# audio_spectrum.net
KiCad netlist of a schematic drawn in EAGLE
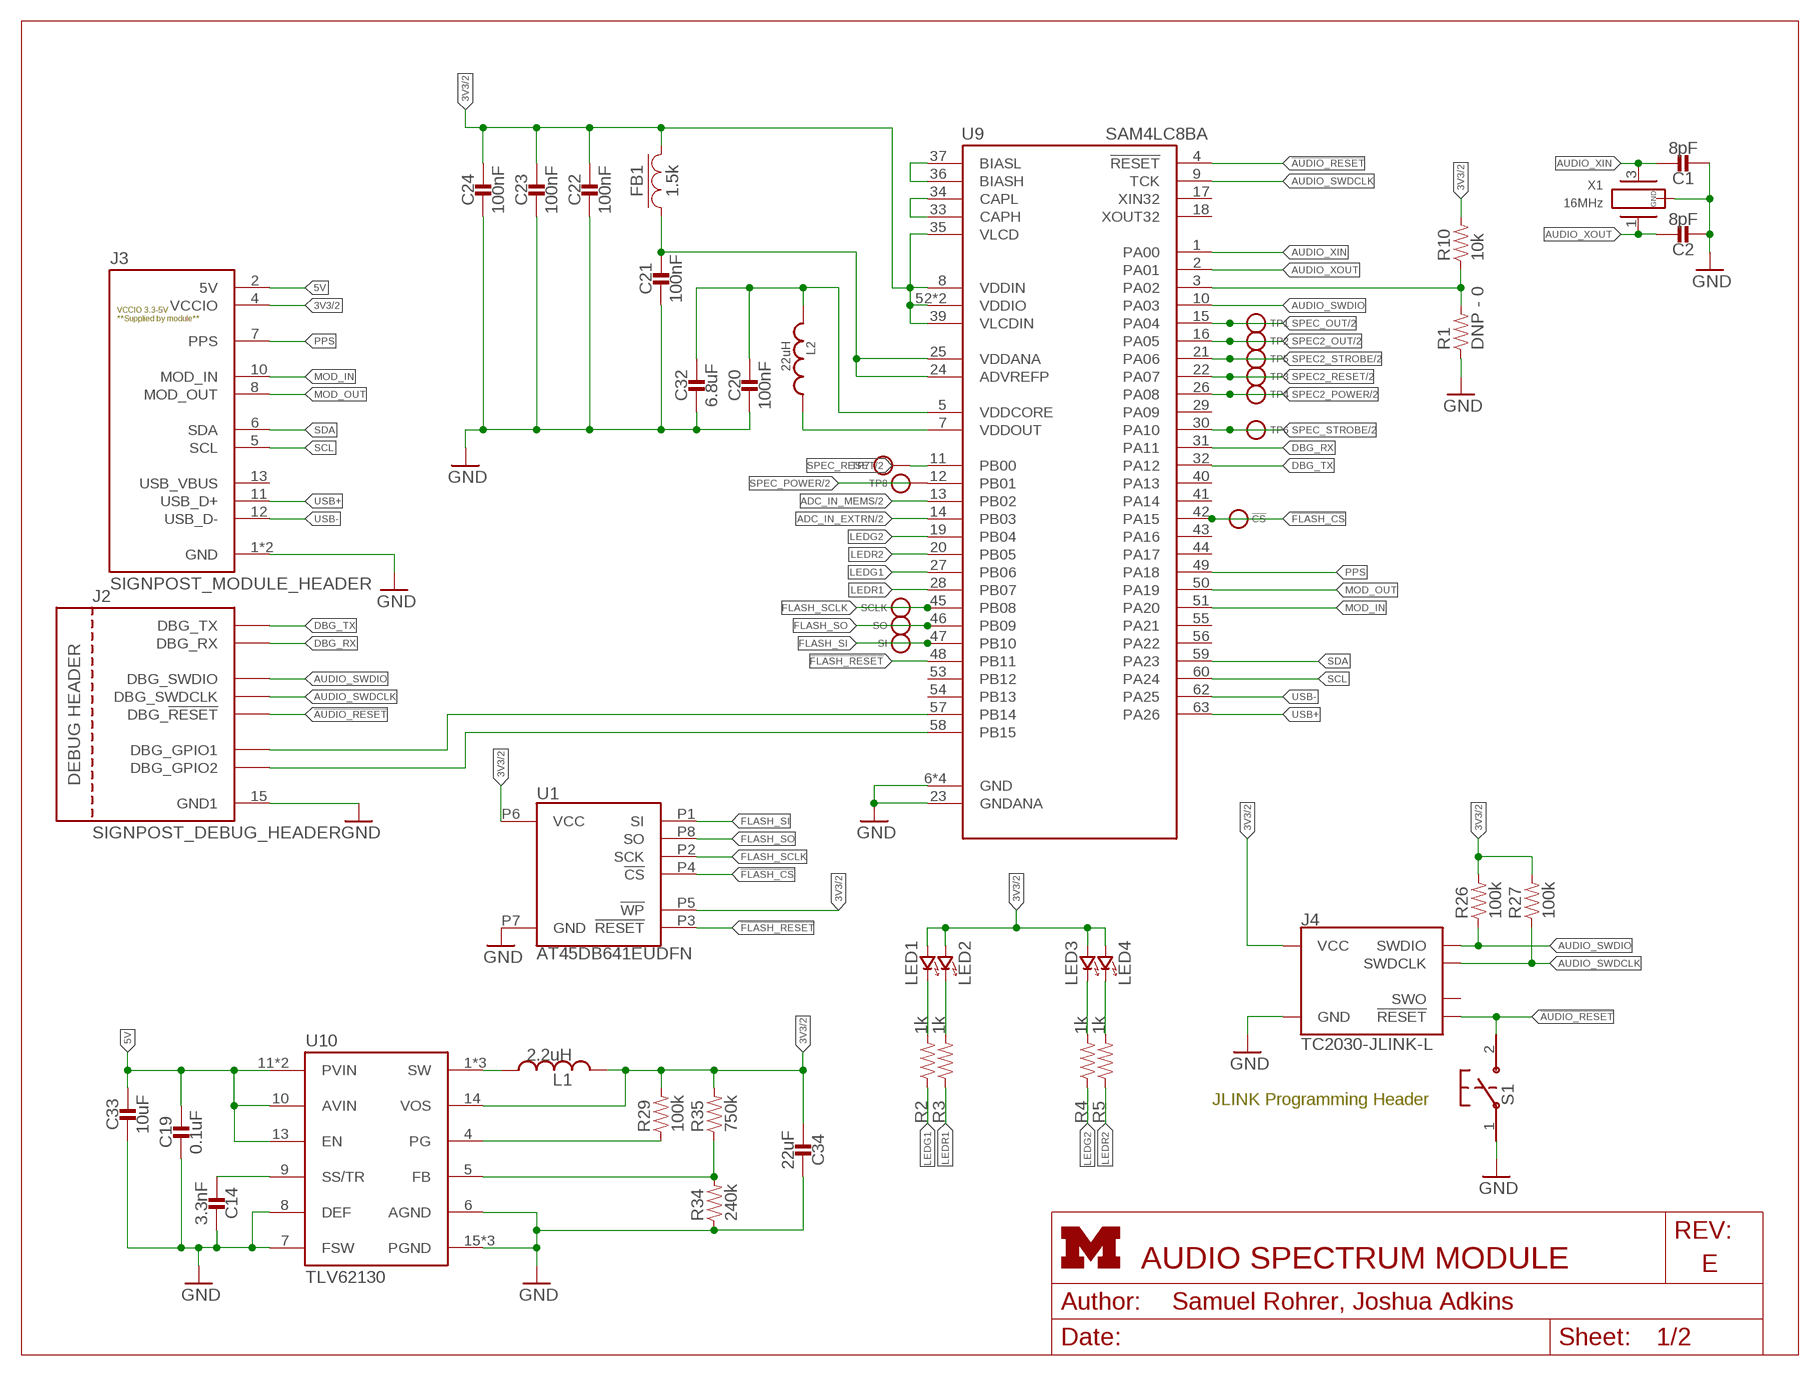
[diagram p0: schematic, sheet 1]
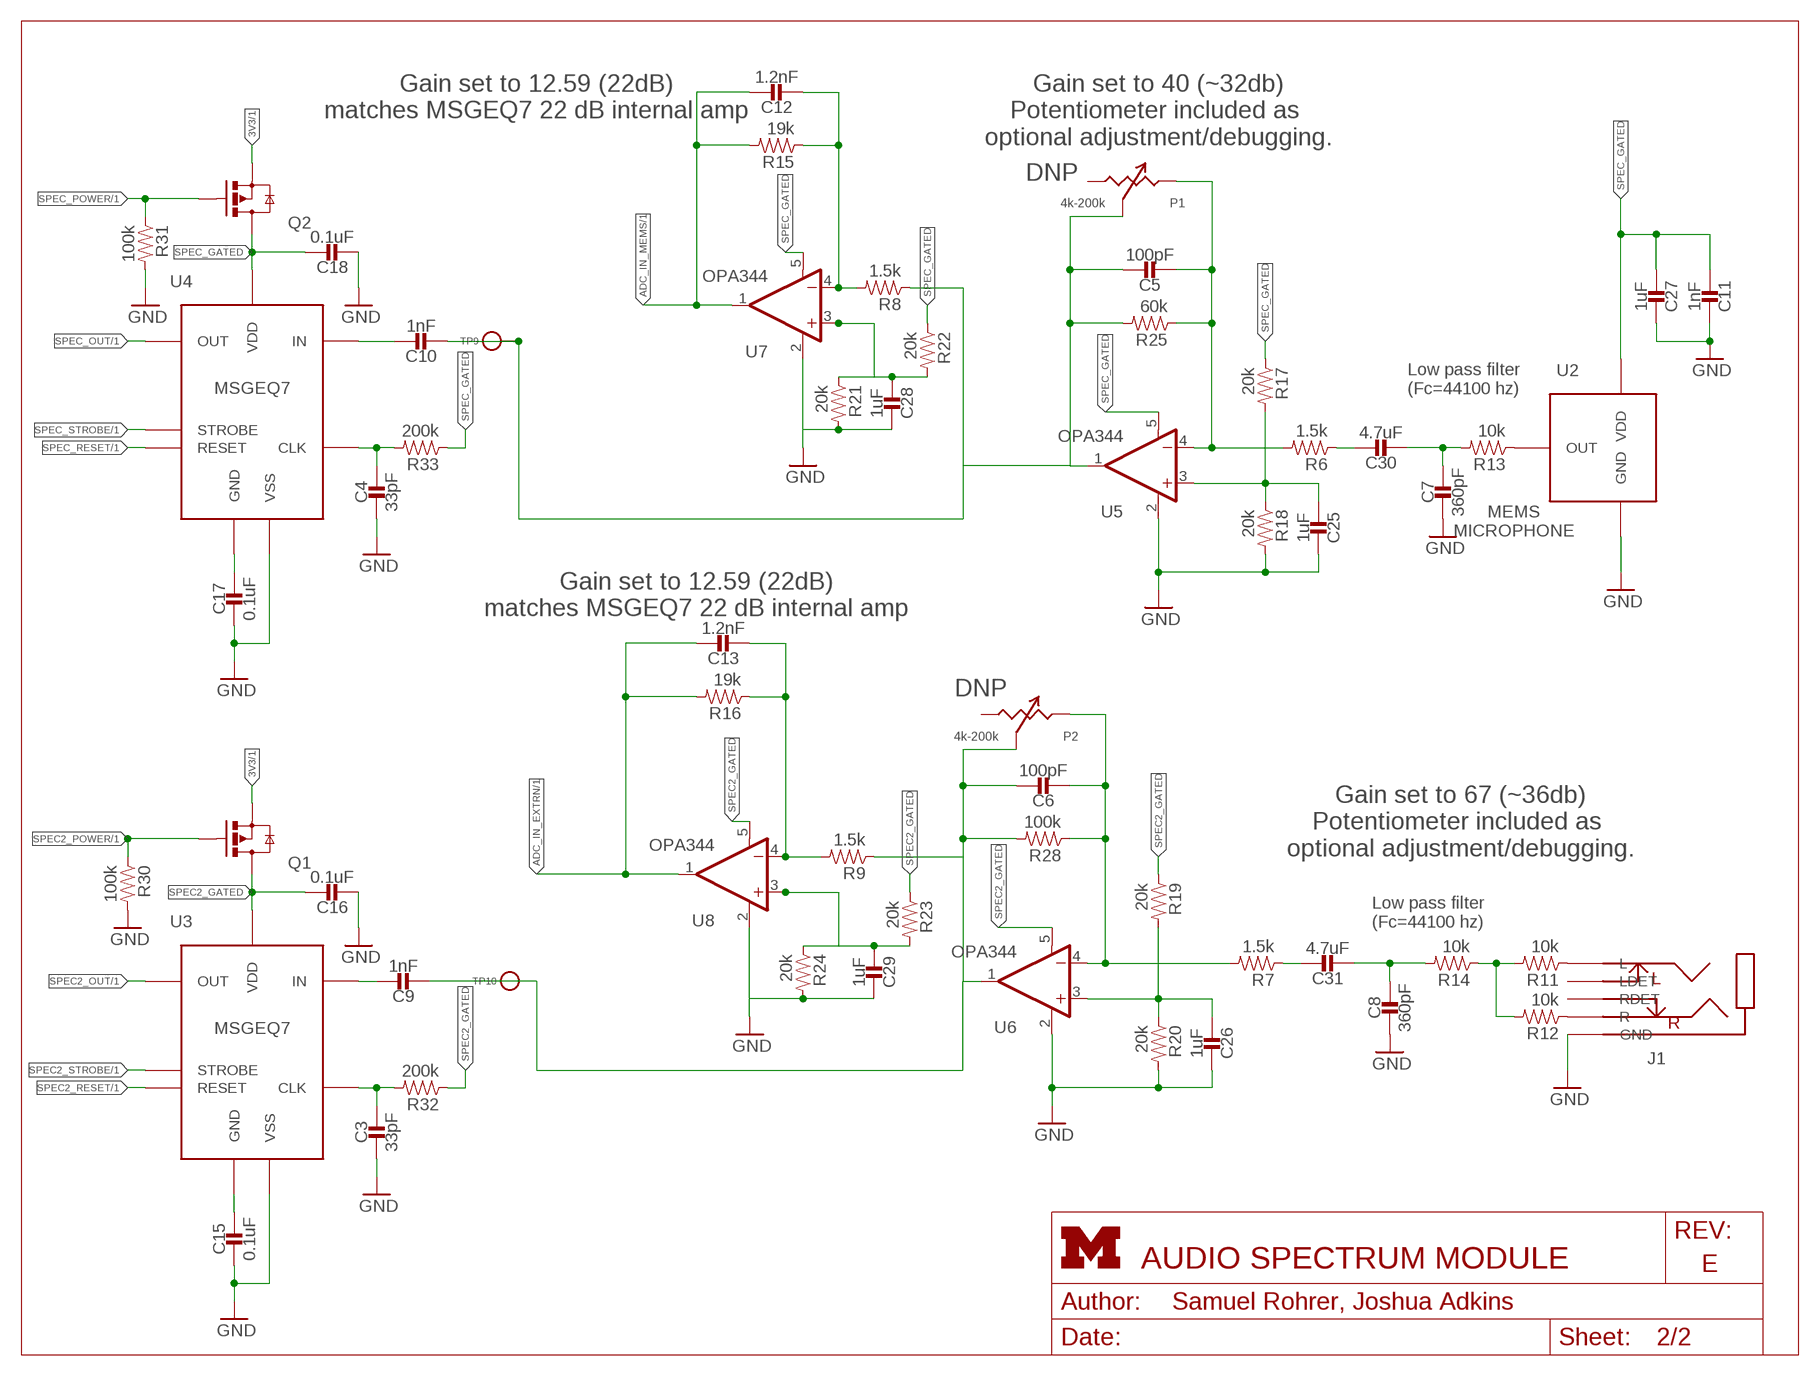
[diagram p1: schematic, sheet 2]

(export (version "E")
  (design (tool "Eeschema 10.0.6"))
  (components
    (comp (ref "C3")
      (value "33pF")
      (footprint "eagle-import:0603_CAP")
      (fields (field (name "MANUFACTURER") "Murata") (field (name "MPN") "GRM1885C1H330JA01D"))
      (libsource (lib "eagle-import") (part "CAPACITOR0603_CAP"))
    )
    (comp (ref "C4")
      (value "33pF")
      (footprint "eagle-import:0603_CAP")
      (fields (field (name "MANUFACTURER") "Murata") (field (name "MPN") "GRM1885C1H330JA01D"))
      (libsource (lib "eagle-import") (part "CAPACITOR0603_CAP"))
    )
    (comp (ref "C5")
      (value "100pF")
      (footprint "eagle-import:0603_CAP")
      (fields (field (name "MANUFACTURER") "Murata") (field (name "MPN") "GRM1885C1H101JA01D"))
      (libsource (lib "eagle-import") (part "CAPACITOR0603_CAP"))
    )
    (comp (ref "C6")
      (value "100pF")
      (footprint "eagle-import:0603_CAP")
      (fields (field (name "MANUFACTURER") "Murata") (field (name "MPN") "GRM1885C1H101JA01D"))
      (libsource (lib "eagle-import") (part "CAPACITOR0603_CAP"))
    )
    (comp (ref "C7")
      (value "360pF")
      (footprint "eagle-import:0603_CAP")
      (fields (field (name "MANUFACTURER") "Murata") (field (name "MPN") "GRM1885C1H361JA01D"))
      (libsource (lib "eagle-import") (part "CAPACITOR0603_CAP"))
    )
    (comp (ref "C8")
      (value "360pF")
      (footprint "eagle-import:0603_CAP")
      (fields (field (name "MANUFACTURER") "Murata") (field (name "MPN") "GRM1885C1H361JA01D"))
      (libsource (lib "eagle-import") (part "CAPACITOR0603_CAP"))
    )
    (comp (ref "C9")
      (value "1nF")
      (footprint "eagle-import:0603_CAP")
      (fields (field (name "MANUFACTURER") "Murata") (field (name "MPN") "GRM188R71H102KA01D"))
      (libsource (lib "eagle-import") (part "CAPACITOR0603_CAP"))
    )
    (comp (ref "C10")
      (value "1nF")
      (footprint "eagle-import:0603_CAP")
      (fields (field (name "MANUFACTURER") "Murata") (field (name "MPN") "GRM188R71H102KA01D"))
      (libsource (lib "eagle-import") (part "CAPACITOR0603_CAP"))
    )
    (comp (ref "C11")
      (value "1nF")
      (footprint "eagle-import:0603_CAP")
      (fields (field (name "MANUFACTURER") "Murata") (field (name "MPN") "GRM188R71H102KA01D"))
      (libsource (lib "eagle-import") (part "CAPACITOR0603_CAP"))
    )
    (comp (ref "C12")
      (value "1.2nF")
      (footprint "eagle-import:0603_CAP")
      (fields (field (name "MANUFACTURER") "Murata") (field (name "MPN") "GCM1885C1H122JA16D"))
      (libsource (lib "eagle-import") (part "CAPACITOR0603_CAP"))
    )
    (comp (ref "C13")
      (value "1.2nF")
      (footprint "eagle-import:0603_CAP")
      (fields (field (name "MANUFACTURER") "Murata") (field (name "MPN") "GCM1885C1H122JA16D"))
      (libsource (lib "eagle-import") (part "CAPACITOR0603_CAP"))
    )
    (comp (ref "C15")
      (value "0.1uF")
      (footprint "eagle-import:0603_CAP")
      (fields (field (name "MANUFACTURER") "Murata") (field (name "MPN") "GRM188R71C104KA01D"))
      (libsource (lib "eagle-import") (part "CAPACITOR0603_CAP"))
    )
    (comp (ref "C16")
      (value "0.1uF")
      (footprint "eagle-import:0603_CAP")
      (fields (field (name "MANUFACTURER") "Murata") (field (name "MPN") "GRM188R71C104KA01D"))
      (libsource (lib "eagle-import") (part "CAPACITOR0603_CAP"))
    )
    (comp (ref "C17")
      (value "0.1uF")
      (footprint "eagle-import:0603_CAP")
      (fields (field (name "MANUFACTURER") "Murata") (field (name "MPN") "GRM188R71C104KA01D"))
      (libsource (lib "eagle-import") (part "CAPACITOR0603_CAP"))
    )
    (comp (ref "C18")
      (value "0.1uF")
      (footprint "eagle-import:0603_CAP")
      (fields (field (name "MANUFACTURER") "Murata") (field (name "MPN") "GRM188R71C104KA01D"))
      (libsource (lib "eagle-import") (part "CAPACITOR0603_CAP"))
    )
    (comp (ref "C25")
      (value "1uF")
      (footprint "eagle-import:0603_CAP")
      (fields (field (name "MANUFACTURER") "Murata") (field (name "MPN") "GRM188R61C105KA93D"))
      (libsource (lib "eagle-import") (part "CAPACITOR0603_CAP"))
    )
    (comp (ref "C26")
      (value "1uF")
      (footprint "eagle-import:0603_CAP")
      (fields (field (name "MANUFACTURER") "Murata") (field (name "MPN") "GRM188R61C105KA93D"))
      (libsource (lib "eagle-import") (part "CAPACITOR0603_CAP"))
    )
    (comp (ref "C27")
      (value "1uF")
      (footprint "eagle-import:0603_CAP")
      (fields (field (name "MANUFACTURER") "Murata") (field (name "MPN") "GRM188R61C105KA93D"))
      (libsource (lib "eagle-import") (part "CAPACITOR0603_CAP"))
    )
    (comp (ref "C28")
      (value "1uF")
      (footprint "eagle-import:0603_CAP")
      (fields (field (name "MANUFACTURER") "Murata") (field (name "MPN") "GRM188R61C105KA93D"))
      (libsource (lib "eagle-import") (part "CAPACITOR0603_CAP"))
    )
    (comp (ref "C29")
      (value "1uF")
      (footprint "eagle-import:0603_CAP")
      (fields (field (name "MANUFACTURER") "Murata") (field (name "MPN") "GRM188R61C105KA93D"))
      (libsource (lib "eagle-import") (part "CAPACITOR0603_CAP"))
    )
    (comp (ref "C30")
      (value "4.7uF")
      (footprint "eagle-import:0603_CAP")
      (fields (field (name "MANUFACTURER") "Murata") (field (name "MPN") "GRM188R60J475KE19D"))
      (libsource (lib "eagle-import") (part "CAPACITOR0603_CAP"))
    )
    (comp (ref "C31")
      (value "4.7uF")
      (footprint "eagle-import:0603_CAP")
      (fields (field (name "MANUFACTURER") "Murata") (field (name "MPN") "GRM188R60J475KE19D"))
      (libsource (lib "eagle-import") (part "CAPACITOR0603_CAP"))
    )
    (comp (ref "J1")
      (value "AUDIO-JACK-VERTICAL")
      (footprint "eagle-import:AUDIO-JACK-VERTICAL")
      (fields
        (field (name "MANUFACTURER") "Kycon")
        (field (name "MPN") "STX-3790-5N")
        (field (name "MANUFACTURER_1") "Kycon")
        (field (name "MPN_1") "STX-3790-5N")
      )
      (libsource (lib "eagle-import") (part "AUDIO-JACK-VERTICAL"))
    )
    (comp (ref "P1")
      (value "4k-200k")
      (footprint "eagle-import:TC33X-2")
      (libsource (lib "eagle-import") (part "POTTC33X"))
    )
    (comp (ref "P2")
      (value "4k-200k")
      (footprint "eagle-import:TC33X-2")
      (libsource (lib "eagle-import") (part "POTTC33X"))
    )
    (comp (ref "Q1")
      (value "NX3008PBK")
      (footprint "eagle-import:SOT23-3")
      (fields (field (name "MANUFACTURER") "Nexperia") (field (name "MPN") "NX3008PBK,215"))
      (libsource (lib "eagle-import") (part "NX3008PBK"))
    )
    (comp (ref "Q2")
      (value "NX3008PBK")
      (footprint "eagle-import:SOT23-3")
      (fields (field (name "MANUFACTURER") "Nexperia") (field (name "MPN") "NX3008PBK,215"))
      (libsource (lib "eagle-import") (part "NX3008PBK"))
    )
    (comp (ref "R6")
      (value "1.5k")
      (footprint "eagle-import:0603-RES")
      (fields (field (name "MANUFACTURER") "Rohm") (field (name "MPN") "MCR03ERTJ152 "))
      (libsource (lib "eagle-import") (part "RESISTOR0603_RES"))
    )
    (comp (ref "R7")
      (value "1.5k")
      (footprint "eagle-import:0603-RES")
      (fields (field (name "MANUFACTURER") "Rohm") (field (name "MPN") "MCR03ERTJ152 "))
      (libsource (lib "eagle-import") (part "RESISTOR0603_RES"))
    )
    (comp (ref "R8")
      (value "1.5k")
      (footprint "eagle-import:0603-RES")
      (fields (field (name "MANUFACTURER") "Rohm") (field (name "MPN") "MCR03ERTJ152"))
      (libsource (lib "eagle-import") (part "RESISTOR0603_RES"))
    )
    (comp (ref "R9")
      (value "1.5k")
      (footprint "eagle-import:0603-RES")
      (fields (field (name "MANUFACTURER") "Rohm") (field (name "MPN") "MCR03ERTJ152"))
      (libsource (lib "eagle-import") (part "RESISTOR0603_RES"))
    )
    (comp (ref "R11")
      (value "10k")
      (footprint "eagle-import:0603-RES")
      (fields (field (name "MANUFACTURER") "Rohm") (field (name "MPN") "MCR03EZPFX1002"))
      (libsource (lib "eagle-import") (part "RESISTOR0603_RES"))
    )
    (comp (ref "R12")
      (value "10k")
      (footprint "eagle-import:0603-RES")
      (fields (field (name "MANUFACTURER") "Rohm") (field (name "MPN") "MCR03EZPFX1002"))
      (libsource (lib "eagle-import") (part "RESISTOR0603_RES"))
    )
    (comp (ref "R13")
      (value "10k")
      (footprint "eagle-import:0603-RES")
      (fields (field (name "MANUFACTURER") "Rohm") (field (name "MPN") "MCR03EZPFX1002"))
      (libsource (lib "eagle-import") (part "RESISTOR0603_RES"))
    )
    (comp (ref "R14")
      (value "10k")
      (footprint "eagle-import:0603-RES")
      (fields (field (name "MANUFACTURER") "Rohm") (field (name "MPN") "MCR03EZPFX1002"))
      (libsource (lib "eagle-import") (part "RESISTOR0603_RES"))
    )
    (comp (ref "R15")
      (value "19k")
      (footprint "eagle-import:0603-RES")
      (fields (field (name "MANUFACTURER") "Rohm") (field (name "MPN") "MCR03ERTF1912"))
      (libsource (lib "eagle-import") (part "RESISTOR0603_RES"))
    )
    (comp (ref "R16")
      (value "19k")
      (footprint "eagle-import:0603-RES")
      (fields (field (name "MANUFACTURER") "Rohm") (field (name "MPN") "MCR03ERTF1912"))
      (libsource (lib "eagle-import") (part "RESISTOR0603_RES"))
    )
    (comp (ref "R17")
      (value "20k")
      (footprint "eagle-import:0603-RES")
      (fields (field (name "MANUFACTURER") "Rohm") (field (name "MPN") "MCR03ERTJ203"))
      (libsource (lib "eagle-import") (part "RESISTOR0603_RES"))
    )
    (comp (ref "R18")
      (value "20k")
      (footprint "eagle-import:0603-RES")
      (fields (field (name "MANUFACTURER") "Rohm") (field (name "MPN") "MCR03ERTJ203"))
      (libsource (lib "eagle-import") (part "RESISTOR0603_RES"))
    )
    (comp (ref "R19")
      (value "20k")
      (footprint "eagle-import:0603-RES")
      (fields (field (name "MANUFACTURER") "Rohm") (field (name "MPN") "MCR03ERTJ203"))
      (libsource (lib "eagle-import") (part "RESISTOR0603_RES"))
    )
    (comp (ref "R20")
      (value "20k")
      (footprint "eagle-import:0603-RES")
      (fields (field (name "MANUFACTURER") "Rohm") (field (name "MPN") "MCR03ERTJ203"))
      (libsource (lib "eagle-import") (part "RESISTOR0603_RES"))
    )
    (comp (ref "R21")
      (value "20k")
      (footprint "eagle-import:0603-RES")
      (fields (field (name "MANUFACTURER") "Rohm") (field (name "MPN") "MCR03ERTJ203"))
      (libsource (lib "eagle-import") (part "RESISTOR0603_RES"))
    )
    (comp (ref "R22")
      (value "20k")
      (footprint "eagle-import:0603-RES")
      (fields (field (name "MANUFACTURER") "Rohm") (field (name "MPN") "MCR03ERTJ203"))
      (libsource (lib "eagle-import") (part "RESISTOR0603_RES"))
    )
    (comp (ref "R23")
      (value "20k")
      (footprint "eagle-import:0603-RES")
      (fields (field (name "MANUFACTURER") "Rohm") (field (name "MPN") "MCR03ERTJ203"))
      (libsource (lib "eagle-import") (part "RESISTOR0603_RES"))
    )
    (comp (ref "R24")
      (value "20k")
      (footprint "eagle-import:0603-RES")
      (fields (field (name "MANUFACTURER") "Rohm") (field (name "MPN") "MCR03ERTJ203"))
      (libsource (lib "eagle-import") (part "RESISTOR0603_RES"))
    )
    (comp (ref "R25")
      (value "60k")
      (footprint "eagle-import:0603-RES")
      (fields (field (name "MANUFACTURER") "Rohm") (field (name "MPN") "MCR03ERTF6042"))
      (libsource (lib "eagle-import") (part "RESISTOR0603_RES"))
    )
    (comp (ref "R28")
      (value "100k")
      (footprint "eagle-import:0603-RES")
      (fields (field (name "MANUFACTURER") "Rohm") (field (name "MPN") "MCR03ERTJ104"))
      (libsource (lib "eagle-import") (part "RESISTOR0603_RES"))
    )
    (comp (ref "R30")
      (value "100k")
      (footprint "eagle-import:0603-RES")
      (fields (field (name "MANUFACTURER") "Rohm") (field (name "MPN") "MCR03ERTJ104"))
      (libsource (lib "eagle-import") (part "RESISTOR0603_RES"))
    )
    (comp (ref "R31")
      (value "100k")
      (footprint "eagle-import:0603-RES")
      (fields (field (name "MANUFACTURER") "Rohm") (field (name "MPN") "MCR03ERTJ104"))
      (libsource (lib "eagle-import") (part "RESISTOR0603_RES"))
    )
    (comp (ref "R32")
      (value "200k")
      (footprint "eagle-import:0603-RES")
      (fields (field (name "MANUFACTURER") "Rohm") (field (name "MPN") "MCR03ERTF2003"))
      (libsource (lib "eagle-import") (part "RESISTOR0603_RES"))
    )
    (comp (ref "R33")
      (value "200k")
      (footprint "eagle-import:0603-RES")
      (fields (field (name "MANUFACTURER") "Rohm") (field (name "MPN") "MCR03ERTF2003"))
      (libsource (lib "eagle-import") (part "RESISTOR0603_RES"))
    )
    (comp (ref "TP9")
      (value "TEST_POINT_0.040IN")
      (footprint "eagle-import:TESTPOINT_0.040IN")
      (libsource (lib "eagle-import") (part "TEST_POINT_0.040IN"))
    )
    (comp (ref "TP10")
      (value "TEST_POINT_0.040IN")
      (footprint "eagle-import:TESTPOINT_0.040IN")
      (libsource (lib "eagle-import") (part "TEST_POINT_0.040IN"))
    )
    (comp (ref "U2")
      (value "MP23AB02B")
      (footprint "eagle-import:MP23AB02B")
      (fields (field (name "MANUFACTURER") "STMicroelectronics") (field (name "MPN") "MP23AB02BTR"))
      (libsource (lib "eagle-import") (part "MP23AB02B"))
    )
    (comp (ref "U3")
      (value "MSGEQ7")
      (footprint "eagle-import:DIP-8")
      (fields (field (name "MANUFACTURER") "Sparkfun Electronics") (field (name "MPN") "COM-10468"))
      (libsource (lib "eagle-import") (part "MSGEQ7"))
    )
    (comp (ref "U4")
      (value "MSGEQ7")
      (footprint "eagle-import:DIP-8")
      (fields (field (name "MANUFACTURER") "Sparkfun Electronics") (field (name "MPN") "COM-10468"))
      (libsource (lib "eagle-import") (part "MSGEQ7"))
    )
    (comp (ref "U5")
      (value "OPA344")
      (footprint "eagle-import:SOT23-5")
      (fields
        (field (name "MANUFACTURER") "Texax Instruments")
        (field (name "MPN") "OPA344NA/250")
        (field (name "DIGIKEY") "OPA344NACT-ND")
      )
      (libsource (lib "eagle-import") (part "OPA344"))
    )
    (comp (ref "U6")
      (value "OPA344")
      (footprint "eagle-import:SOT23-5")
      (fields
        (field (name "MANUFACTURER") "Texax Instruments")
        (field (name "MPN") "OPA344NA/250")
        (field (name "DIGIKEY") "OPA344NACT-ND")
      )
      (libsource (lib "eagle-import") (part "OPA344"))
    )
    (comp (ref "U7")
      (value "OPA344")
      (footprint "eagle-import:SOT23-5")
      (fields
        (field (name "MANUFACTURER") "Texax Instruments")
        (field (name "MPN") "OPA344NA/250")
        (field (name "DIGIKEY") "OPA344NACT-ND")
      )
      (libsource (lib "eagle-import") (part "OPA344"))
    )
    (comp (ref "U8")
      (value "OPA344")
      (footprint "eagle-import:SOT23-5")
      (fields
        (field (name "MANUFACTURER") "Texax Instruments")
        (field (name "MPN") "OPA344NA/250")
        (field (name "DIGIKEY") "OPA344NACT-ND")
      )
      (libsource (lib "eagle-import") (part "OPA344"))
    )
    (comp (ref "!CS")
      (value "TEST_POINT_0.040IN")
      (footprint "eagle-import:TESTPOINT_0.040IN")
      (libsource (lib "eagle-import") (part "TEST_POINT_0.040IN"))
    )
    (comp (ref "C1")
      (value "8pF")
      (footprint "eagle-import:0402_CAP")
      (fields (field (name "MANUFACTURER") "Murata") (field (name "MPN") "GRM1555C1H8R0BA01D"))
      (libsource (lib "eagle-import") (part "CAPACITOR0402_CAP"))
    )
    (comp (ref "C2")
      (value "8pF")
      (footprint "eagle-import:0402_CAP")
      (fields (field (name "MANUFACTURER") "Murata") (field (name "MPN") "GRM1555C1H8R0BA01D"))
      (libsource (lib "eagle-import") (part "CAPACITOR0402_CAP"))
    )
    (comp (ref "C14")
      (value "3.3nF")
      (footprint "eagle-import:0603_CAP")
      (fields (field (name "MANUFACTURER") "Murata") (field (name "MPN") "GRM188R71H332KA01D"))
      (libsource (lib "eagle-import") (part "CAPACITOR0603_CAP"))
    )
    (comp (ref "C19")
      (value "0.1uF")
      (footprint "eagle-import:0603_CAP")
      (fields (field (name "MANUFACTURER") "Murata") (field (name "MPN") "GRM188R71C104KA01D"))
      (libsource (lib "eagle-import") (part "CAPACITOR0603_CAP"))
    )
    (comp (ref "C20")
      (value "100nF")
      (footprint "eagle-import:0402_CAP")
      (fields (field (name "MANUFACTURER") "Murata") (field (name "MPN") "GRM155R71A104JA01D"))
      (libsource (lib "eagle-import") (part "CAPACITOR0402_CAP"))
    )
    (comp (ref "C21")
      (value "100nF")
      (footprint "eagle-import:0603_CAP")
      (fields (field (name "MANUFACTURER") "Murata") (field (name "MPN") "GRM188R71C104KA01D"))
      (libsource (lib "eagle-import") (part "CAPACITOR0603_CAP"))
    )
    (comp (ref "C22")
      (value "100nF")
      (footprint "eagle-import:0603_CAP")
      (fields (field (name "MANUFACTURER") "Murata") (field (name "MPN") "GRM188R71C104KA01D"))
      (libsource (lib "eagle-import") (part "CAPACITOR0603_CAP"))
    )
    (comp (ref "C23")
      (value "100nF")
      (footprint "eagle-import:0603_CAP")
      (fields (field (name "MANUFACTURER") "Murata") (field (name "MPN") "GRM188R71C104KA01D"))
      (libsource (lib "eagle-import") (part "CAPACITOR0603_CAP"))
    )
    (comp (ref "C24")
      (value "100nF")
      (footprint "eagle-import:0603_CAP")
      (fields (field (name "MANUFACTURER") "Murata") (field (name "MPN") "GRM188R71C104KA01D"))
      (libsource (lib "eagle-import") (part "CAPACITOR0603_CAP"))
    )
    (comp (ref "C32")
      (value "6.8uF")
      (footprint "eagle-import:0603_CAP")
      (fields (field (name "MANUFACTURER") "TDk") (field (name "MPN") "C1608X5R1A685K080AC"))
      (libsource (lib "eagle-import") (part "CAPACITOR0603_CAP"))
    )
    (comp (ref "C33")
      (value "10uF")
      (footprint "eagle-import:0603_CAP")
      (fields (field (name "MANUFACTURER") "Murata") (field (name "MPN") "GRM188R60J106ME47J"))
      (libsource (lib "eagle-import") (part "CAPACITOR0603_CAP"))
    )
    (comp (ref "C34")
      (value "22uF")
      (footprint "eagle-import:0603_CAP")
      (fields (field (name "MANUFACTURER") "Murata") (field (name "MPN") "GRM186R60J226ME15D"))
      (libsource (lib "eagle-import") (part "CAPACITOR0603_CAP"))
    )
    (comp (ref "FB1")
      (value "1.5k")
      (footprint "eagle-import:0402_CAP")
      (fields (field (name "MANUFACTURER") "Murata") (field (name "MPN") "BLM18HE152SN1D"))
      (libsource (lib "eagle-import") (part "FERRITE_BEAD0402"))
    )
    (comp (ref "J2")
      (value "SIGNPOST_DEBUG_HEADER")
      (footprint "eagle-import:SIGNPOST_DEBUG_HEADER")
      (fields (field (name "MANUFACTURER") "Sullins Connector") (field (name "MPN") "PRPC004DFBN-RC"))
      (libsource (lib "eagle-import") (part "SIGNPOST_DEBUG_HEADER"))
    )
    (comp (ref "J3")
      (value "SIGNPOST_MODULE_HEADER")
      (footprint "eagle-import:SIGNPOST_MODULE_HEADER")
      (fields (field (name "MANUFACTURER") "Sullins Connector") (field (name "MPN") "SBH11-PBPC-D07-ST-BK"))
      (libsource (lib "eagle-import") (part "SIGNPOST_MODULE_HEADER"))
    )
    (comp (ref "J4")
      (value "TC2030-JLINK-L")
      (footprint "eagle-import:TC2030-IDC")
      (libsource (lib "eagle-import") (part "TC2030-JLINK-L"))
    )
    (comp (ref "L1")
      (value "2.2uH")
      (footprint "eagle-import:IHL-1212BZ-11")
      (fields (field (name "MANUFACTURER") "Vishay Dale") (field (name "MPN") "IHLP1212BZER2R2M11"))
      (libsource (lib "eagle-import") (part "INDUCTORIHL"))
    )
    (comp (ref "L2")
      (value "22uH")
      (footprint "eagle-import:1212")
      (fields
        (field (name "MANUFACTURER") "Murata")
        (field (name "MPN") "LQH3NPN220MJ0L")
        (field (name "MANUFACTURER_1") "Murata")
        (field (name "MPN_1") "LQH3NPN220MJ0L")
      )
      (libsource (lib "eagle-import") (part "LHQ3NP"))
    )
    (comp (ref "LED1")
      (value "LED0603")
      (footprint "eagle-import:LED-0603")
      (fields (field (name "MANUFACTURER") "Lite-On") (field (name "MPN") "LTST-C191KGKT"))
      (libsource (lib "eagle-import") (part "LED0603"))
    )
    (comp (ref "LED2")
      (value "LED0603")
      (footprint "eagle-import:LED-0603")
      (fields (field (name "MANUFACTURER") "Lite-On") (field (name "MPN") "LTST-C191KRKT"))
      (libsource (lib "eagle-import") (part "LED0603"))
    )
    (comp (ref "LED3")
      (value "LED0603")
      (footprint "eagle-import:LED-0603")
      (fields (field (name "MANUFACTURER") "Lite-On") (field (name "MPN") "LTST-C191KGKT"))
      (libsource (lib "eagle-import") (part "LED0603"))
    )
    (comp (ref "LED4")
      (value "LED0603")
      (footprint "eagle-import:LED-0603")
      (fields (field (name "MANUFACTURER") "Lite-On") (field (name "MPN") "LTST-C191KRKT"))
      (libsource (lib "eagle-import") (part "LED0603"))
    )
    (comp (ref "R1")
      (value "DNP - 0")
      (footprint "eagle-import:0603-RES")
      (fields (field (name "MANUFACTURER") "Samsung") (field (name "MPN") "RC1005F103CS"))
      (libsource (lib "eagle-import") (part "RESISTOR0603_RES"))
    )
    (comp (ref "R2")
      (value "1k")
      (footprint "eagle-import:0603-RES")
      (fields (field (name "MANUFACTURER") "Murata") (field (name "MPN") "ESR03EZPJ102"))
      (libsource (lib "eagle-import") (part "RESISTOR0603_RES"))
    )
    (comp (ref "R3")
      (value "1k")
      (footprint "eagle-import:0603-RES")
      (fields (field (name "MANUFACTURER") "Murata") (field (name "MPN") "ESR03EZPJ102"))
      (libsource (lib "eagle-import") (part "RESISTOR0603_RES"))
    )
    (comp (ref "R4")
      (value "1k")
      (footprint "eagle-import:0603-RES")
      (fields (field (name "MANUFACTURER") "Murata") (field (name "MPN") "ESR03EZPJ102"))
      (libsource (lib "eagle-import") (part "RESISTOR0603_RES"))
    )
    (comp (ref "R5")
      (value "1k")
      (footprint "eagle-import:0603-RES")
      (fields (field (name "MANUFACTURER") "Murata") (field (name "MPN") "ESR03EZPJ102"))
      (libsource (lib "eagle-import") (part "RESISTOR0603_RES"))
    )
    (comp (ref "R10")
      (value "10k")
      (footprint "eagle-import:0603-RES")
      (fields (field (name "MANUFACTURER") "Rohm") (field (name "MPN") "MCR03EZPFX1002"))
      (libsource (lib "eagle-import") (part "RESISTOR0603_RES"))
    )
    (comp (ref "R26")
      (value "100k")
      (footprint "eagle-import:0603-RES")
      (fields (field (name "MANUFACTURER") "Rohm") (field (name "MPN") "MCR03ERTJ104"))
      (libsource (lib "eagle-import") (part "RESISTOR0603_RES"))
    )
    (comp (ref "R27")
      (value "100k")
      (footprint "eagle-import:0603-RES")
      (fields (field (name "MANUFACTURER") "Rohm") (field (name "MPN") "MCR03ERTJ104"))
      (libsource (lib "eagle-import") (part "RESISTOR0603_RES"))
    )
    (comp (ref "R29")
      (value "100k")
      (footprint "eagle-import:0603-RES")
      (fields (field (name "MANUFACTURER") "Rohm") (field (name "MPN") "MCR03ERTJ104"))
      (libsource (lib "eagle-import") (part "RESISTOR0603_RES"))
    )
    (comp (ref "R34")
      (value "240k")
      (footprint "eagle-import:0603-RES")
      (fields (field (name "MANUFACTURER") "Rohm") (field (name "MPN") "RHM240KCFCT-ND"))
      (libsource (lib "eagle-import") (part "RESISTOR0603_RES"))
    )
    (comp (ref "R35")
      (value "750k")
      (footprint "eagle-import:0603-RES")
      (fields (field (name "MANUFACTURER") "Rohm") (field (name "MPN") "MCR03ERTF7503"))
      (libsource (lib "eagle-import") (part "RESISTOR0603_RES"))
    )
    (comp (ref "S1")
      (value "B3U-1000P")
      (footprint "eagle-import:B3U-1000P")
      (fields (field (name "MANUFACTURER") "Omron"))
      (libsource (lib "eagle-import") (part "B3U-1000P"))
    )
    (comp (ref "SCLK")
      (value "TEST_POINT_0.040IN")
      (footprint "eagle-import:TESTPOINT_0.040IN")
      (libsource (lib "eagle-import") (part "TEST_POINT_0.040IN"))
    )
    (comp (ref "SI")
      (value "TEST_POINT_0.040IN")
      (footprint "eagle-import:TESTPOINT_0.040IN")
      (libsource (lib "eagle-import") (part "TEST_POINT_0.040IN"))
    )
    (comp (ref "SO")
      (value "TEST_POINT_0.040IN")
      (footprint "eagle-import:TESTPOINT_0.040IN")
      (libsource (lib "eagle-import") (part "TEST_POINT_0.040IN"))
    )
    (comp (ref "TP1")
      (value "TEST_POINT_0.040IN")
      (footprint "eagle-import:TESTPOINT_0.040IN")
      (libsource (lib "eagle-import") (part "TEST_POINT_0.040IN"))
    )
    (comp (ref "TP2")
      (value "TEST_POINT_0.040IN")
      (footprint "eagle-import:TESTPOINT_0.040IN")
      (libsource (lib "eagle-import") (part "TEST_POINT_0.040IN"))
    )
    (comp (ref "TP3")
      (value "TEST_POINT_0.040IN")
      (footprint "eagle-import:TESTPOINT_0.040IN")
      (libsource (lib "eagle-import") (part "TEST_POINT_0.040IN"))
    )
    (comp (ref "TP4")
      (value "TEST_POINT_0.040IN")
      (footprint "eagle-import:TESTPOINT_0.040IN")
      (libsource (lib "eagle-import") (part "TEST_POINT_0.040IN"))
    )
    (comp (ref "TP5")
      (value "TEST_POINT_0.040IN")
      (footprint "eagle-import:TESTPOINT_0.040IN")
      (libsource (lib "eagle-import") (part "TEST_POINT_0.040IN"))
    )
    (comp (ref "TP6")
      (value "TEST_POINT_0.040IN")
      (footprint "eagle-import:TESTPOINT_0.040IN")
      (libsource (lib "eagle-import") (part "TEST_POINT_0.040IN"))
    )
    (comp (ref "TP7")
      (value "TEST_POINT_0.040IN")
      (footprint "eagle-import:TESTPOINT_0.040IN")
      (libsource (lib "eagle-import") (part "TEST_POINT_0.040IN"))
    )
    (comp (ref "TP8")
      (value "TEST_POINT_0.040IN")
      (footprint "eagle-import:TESTPOINT_0.040IN")
      (libsource (lib "eagle-import") (part "TEST_POINT_0.040IN"))
    )
    (comp (ref "U1")
      (value "AT45DB641EUDFN")
      (footprint "eagle-import:UDFN-8-5MMX6MM")
      (fields (field (name "MANUFACTURER") "Adesto") (field (name "MPN") "AT45DB641E-MHN-T"))
      (libsource (lib "eagle-import") (part "AT45DB641EUDFN"))
    )
    (comp (ref "U9")
      (value "SAM4LC8BA")
      (footprint "eagle-import:QFN-64-9MM")
      (fields (field (name "MANUFACTURER") "Microchip") (field (name "MPN") "ATSAM4LC8BA-MUR"))
      (libsource (lib "eagle-import") (part "SAM4LC8BA"))
    )
    (comp (ref "U10")
      (value "TLV62130")
      (footprint "eagle-import:TQFN-16_3MM")
      (fields (field (name "MANUFACTURER") "Texas Instruments") (field (name "MPN") "TLV62130RGTR"))
      (libsource (lib "eagle-import") (part "TLV62130"))
    )
    (comp (ref "X1")
      (value "16MHz")
      (footprint "eagle-import:FHXXX")
      (fields (field (name "MANUFACTURER") "Diodes Incorporated") (field (name "MPN") "FH1600015"))
      (libsource (lib "eagle-import") (part "FH1600015"))
    )
  )
  (nets
    (net (code "1") (name "3V3") (class "Default")
      (node (ref "C22") (pin "1") (pinfunction "1_1") (pintype "bidirectional"))
      (node (ref "C23") (pin "1") (pinfunction "1_1") (pintype "bidirectional"))
      (node (ref "C24") (pin "1") (pinfunction "1_1") (pintype "bidirectional"))
      (node (ref "C34") (pin "2") (pinfunction "2_2") (pintype "bidirectional"))
      (node (ref "FB1") (pin "2") (pinfunction "P$2_2") (pintype "bidirectional"))
      (node (ref "J3") (pin "4") (pinfunction "VCCIO_4") (pintype "bidirectional"))
      (node (ref "J4") (pin "1") (pinfunction "VCC_1") (pintype "bidirectional"))
      (node (ref "L1") (pin "P$2") (pinfunction "2_P$2") (pintype "bidirectional"))
      (node (ref "LED1") (pin "A") (pinfunction "ANODE_A") (pintype "bidirectional"))
      (node (ref "LED2") (pin "A") (pinfunction "ANODE_A") (pintype "bidirectional"))
      (node (ref "LED3") (pin "A") (pinfunction "ANODE_A") (pintype "bidirectional"))
      (node (ref "LED4") (pin "A") (pinfunction "ANODE_A") (pintype "bidirectional"))
      (node (ref "Q1") (pin "2") (pinfunction "S_2") (pintype "passive"))
      (node (ref "Q2") (pin "2") (pinfunction "S_2") (pintype "passive"))
      (node (ref "R10") (pin "2") (pinfunction "2_2") (pintype "passive"))
      (node (ref "R26") (pin "2") (pinfunction "2_2") (pintype "passive"))
      (node (ref "R27") (pin "2") (pinfunction "2_2") (pintype "passive"))
      (node (ref "R29") (pin "2") (pinfunction "2_2") (pintype "passive"))
      (node (ref "R35") (pin "2") (pinfunction "2_2") (pintype "passive"))
      (node (ref "U1") (pin "P5") (pinfunction "~{WP}_P5") (pintype "bidirectional"))
      (node (ref "U1") (pin "P6") (pinfunction "VCC_P6") (pintype "bidirectional"))
      (node (ref "U10") (pin "14") (pinfunction "VOS_14") (pintype "bidirectional"))
      (node (ref "U9") (pin "35") (pinfunction "VLCD_35") (pintype "bidirectional"))
      (node (ref "U9") (pin "39") (pinfunction "VLCDIN_39") (pintype "power_in"))
      (node (ref "U9") (pin "52") (pinfunction "VDDIO_52") (pintype "power_in"))
      (node (ref "U9") (pin "61") (pinfunction "VDDIO_61") (pintype "power_in"))
      (node (ref "U9") (pin "8") (pinfunction "VDDIN_8") (pintype "power_in"))
    )
    (net (code "2") (name "5V") (class "Default")
      (node (ref "C19") (pin "1") (pinfunction "1_1") (pintype "bidirectional"))
      (node (ref "C33") (pin "1") (pinfunction "1_1") (pintype "bidirectional"))
      (node (ref "J3") (pin "2") (pinfunction "5V_2") (pintype "bidirectional"))
      (node (ref "U10") (pin "10") (pinfunction "AVIN_10") (pintype "bidirectional"))
      (node (ref "U10") (pin "11") (pinfunction "PVIN_11") (pintype "bidirectional"))
      (node (ref "U10") (pin "12") (pinfunction "PVIN_12") (pintype "bidirectional"))
      (node (ref "U10") (pin "13") (pinfunction "EN_13") (pintype "bidirectional"))
    )
    (net (code "3") (name "ADC_IN_EXTRN") (class "Default")
      (node (ref "C13") (pin "1") (pinfunction "1_1") (pintype "bidirectional"))
      (node (ref "R16") (pin "2") (pinfunction "2_2") (pintype "passive"))
      (node (ref "U8") (pin "1") (pinfunction "OUT_1") (pintype "output"))
      (node (ref "U9") (pin "14") (pinfunction "PB03_14") (pintype "bidirectional"))
    )
    (net (code "4") (name "ADC_IN_MEMS") (class "Default")
      (node (ref "C12") (pin "1") (pinfunction "1_1") (pintype "bidirectional"))
      (node (ref "R15") (pin "2") (pinfunction "2_2") (pintype "passive"))
      (node (ref "U7") (pin "1") (pinfunction "OUT_1") (pintype "output"))
      (node (ref "U9") (pin "13") (pinfunction "PB02_13") (pintype "bidirectional"))
    )
    (net (code "5") (name "AUDIO_SWDCLK") (class "Default")
      (node (ref "J2") (pin "21") (pinfunction "DBG_SWDCLK_21") (pintype "bidirectional"))
      (node (ref "J4") (pin "4") (pinfunction "SWDCLK_4") (pintype "bidirectional"))
      (node (ref "R27") (pin "1") (pinfunction "1_1") (pintype "passive"))
      (node (ref "U9") (pin "9") (pinfunction "TCK_9") (pintype "bidirectional"))
    )
    (net (code "6") (name "AUDIO_SWDIO") (class "Default")
      (node (ref "J2") (pin "22") (pinfunction "DBG_SWDIO_22") (pintype "bidirectional"))
      (node (ref "J4") (pin "2") (pinfunction "SWDIO_2") (pintype "bidirectional"))
      (node (ref "R26") (pin "1") (pinfunction "1_1") (pintype "passive"))
      (node (ref "U9") (pin "10") (pinfunction "PA03_10") (pintype "bidirectional"))
    )
    (net (code "7") (name "AUDIO_XIN") (class "Default")
      (node (ref "C1") (pin "1") (pinfunction "1_1") (pintype "bidirectional"))
      (node (ref "U9") (pin "1") (pinfunction "PA00_1") (pintype "bidirectional"))
      (node (ref "X1") (pin "3") (pinfunction "2_3") (pintype "bidirectional"))
    )
    (net (code "8") (name "AUDIO_XOUT") (class "Default")
      (node (ref "C2") (pin "1") (pinfunction "1_1") (pintype "bidirectional"))
      (node (ref "U9") (pin "2") (pinfunction "PA01_2") (pintype "bidirectional"))
      (node (ref "X1") (pin "1") (pinfunction "1_1") (pintype "bidirectional"))
    )
    (net (code "9") (name "DBG_RX") (class "Default")
      (node (ref "J2") (pin "18") (pinfunction "DBG_RX_18") (pintype "bidirectional"))
      (node (ref "U9") (pin "31") (pinfunction "PA11_31") (pintype "bidirectional"))
    )
    (net (code "10") (name "DBG_TX") (class "Default")
      (node (ref "J2") (pin "17") (pinfunction "DBG_TX_17") (pintype "bidirectional"))
      (node (ref "U9") (pin "32") (pinfunction "PA12_32") (pintype "bidirectional"))
    )
    (net (code "11") (name "FLASH_SCLK") (class "Default")
      (node (ref "SCLK") (pin "TESTPOINT") (pinfunction "TESTPOINT_TESTPOINT") (pintype "bidirectional"))
      (node (ref "U1") (pin "P2") (pinfunction "SCK_P2") (pintype "bidirectional"))
      (node (ref "U9") (pin "45") (pinfunction "PB08_45") (pintype "bidirectional"))
    )
    (net (code "12") (name "FLASH_SI") (class "Default")
      (node (ref "SI") (pin "TESTPOINT") (pinfunction "TESTPOINT_TESTPOINT") (pintype "bidirectional"))
      (node (ref "U1") (pin "P1") (pinfunction "SI_P1") (pintype "bidirectional"))
      (node (ref "U9") (pin "47") (pinfunction "PB10_47") (pintype "bidirectional"))
    )
    (net (code "13") (name "FLASH_SO") (class "Default")
      (node (ref "SO") (pin "TESTPOINT") (pinfunction "TESTPOINT_TESTPOINT") (pintype "bidirectional"))
      (node (ref "U1") (pin "P8") (pinfunction "SO_P8") (pintype "bidirectional"))
      (node (ref "U9") (pin "46") (pinfunction "PB09_46") (pintype "bidirectional"))
    )
    (net (code "14") (name "GND") (class "Default")
      (node (ref "C1") (pin "2") (pinfunction "2_2") (pintype "bidirectional"))
      (node (ref "C11") (pin "1") (pinfunction "1_1") (pintype "bidirectional"))
      (node (ref "C14") (pin "1") (pinfunction "1_1") (pintype "bidirectional"))
      (node (ref "C15") (pin "2") (pinfunction "2_2") (pintype "bidirectional"))
      (node (ref "C16") (pin "2") (pinfunction "2_2") (pintype "bidirectional"))
      (node (ref "C17") (pin "2") (pinfunction "2_2") (pintype "bidirectional"))
      (node (ref "C18") (pin "2") (pinfunction "2_2") (pintype "bidirectional"))
      (node (ref "C19") (pin "2") (pinfunction "2_2") (pintype "bidirectional"))
      (node (ref "C2") (pin "2") (pinfunction "2_2") (pintype "bidirectional"))
      (node (ref "C20") (pin "2") (pinfunction "2_2") (pintype "bidirectional"))
      (node (ref "C21") (pin "2") (pinfunction "2_2") (pintype "bidirectional"))
      (node (ref "C22") (pin "2") (pinfunction "2_2") (pintype "bidirectional"))
      (node (ref "C23") (pin "2") (pinfunction "2_2") (pintype "bidirectional"))
      (node (ref "C24") (pin "2") (pinfunction "2_2") (pintype "bidirectional"))
      (node (ref "C25") (pin "1") (pinfunction "1_1") (pintype "bidirectional"))
      (node (ref "C26") (pin "1") (pinfunction "1_1") (pintype "bidirectional"))
      (node (ref "C27") (pin "1") (pinfunction "1_1") (pintype "bidirectional"))
      (node (ref "C28") (pin "1") (pinfunction "1_1") (pintype "bidirectional"))
      (node (ref "C29") (pin "1") (pinfunction "1_1") (pintype "bidirectional"))
      (node (ref "C3") (pin "2") (pinfunction "2_2") (pintype "bidirectional"))
      (node (ref "C32") (pin "2") (pinfunction "2_2") (pintype "bidirectional"))
      (node (ref "C33") (pin "2") (pinfunction "2_2") (pintype "bidirectional"))
      (node (ref "C34") (pin "1") (pinfunction "1_1") (pintype "bidirectional"))
      (node (ref "C4") (pin "2") (pinfunction "2_2") (pintype "bidirectional"))
      (node (ref "C7") (pin "2") (pinfunction "2_2") (pintype "bidirectional"))
      (node (ref "C8") (pin "2") (pinfunction "2_2") (pintype "bidirectional"))
      (node (ref "J1") (pin "5") (pinfunction "GND_5") (pintype "bidirectional"))
      (node (ref "J2") (pin "15") (pinfunction "GND1_15") (pintype "bidirectional"))
      (node (ref "J3") (pin "1") (pinfunction "GND_1") (pintype "bidirectional"))
      (node (ref "J3") (pin "14") (pinfunction "GND_14") (pintype "bidirectional"))
      (node (ref "J4") (pin "5") (pinfunction "GND_5") (pintype "bidirectional"))
      (node (ref "R1") (pin "1") (pinfunction "1_1") (pintype "passive"))
      (node (ref "R18") (pin "2") (pinfunction "2_2") (pintype "passive"))
      (node (ref "R20") (pin "2") (pinfunction "2_2") (pintype "passive"))
      (node (ref "R21") (pin "2") (pinfunction "2_2") (pintype "passive"))
      (node (ref "R24") (pin "2") (pinfunction "2_2") (pintype "passive"))
      (node (ref "R30") (pin "2") (pinfunction "2_2") (pintype "passive"))
      (node (ref "R31") (pin "2") (pinfunction "2_2") (pintype "passive"))
      (node (ref "R34") (pin "1") (pinfunction "1_1") (pintype "passive"))
      (node (ref "S1") (pin "1") (pinfunction "P$1_1") (pintype "passive"))
      (node (ref "U1") (pin "P7") (pinfunction "GND_P7") (pintype "bidirectional"))
      (node (ref "U10") (pin "15") (pinfunction "PGND_15") (pintype "bidirectional"))
      (node (ref "U10") (pin "16") (pinfunction "PGND_16") (pintype "bidirectional"))
      (node (ref "U10") (pin "6") (pinfunction "AGND_6") (pintype "bidirectional"))
      (node (ref "U10") (pin "7") (pinfunction "FSW_7") (pintype "bidirectional"))
      (node (ref "U10") (pin "8") (pinfunction "DEF_8") (pintype "bidirectional"))
      (node (ref "U10") (pin "GND") (pinfunction "PGND_GND") (pintype "bidirectional"))
      (node (ref "U2") (pin "3") (pinfunction "GND_3") (pintype "bidirectional"))
      (node (ref "U3") (pin "2") (pinfunction "VSS_2") (pintype "bidirectional"))
      (node (ref "U4") (pin "2") (pinfunction "VSS_2") (pintype "bidirectional"))
      (node (ref "U5") (pin "2") (pinfunction "V-_2") (pintype "power_in"))
      (node (ref "U6") (pin "2") (pinfunction "V-_2") (pintype "power_in"))
      (node (ref "U7") (pin "2") (pinfunction "V-_2") (pintype "power_in"))
      (node (ref "U8") (pin "2") (pinfunction "V-_2") (pintype "power_in"))
      (node (ref "U9") (pin "23") (pinfunction "GNDANA_23") (pintype "power_in"))
      (node (ref "U9") (pin "38") (pinfunction "GND_38") (pintype "power_in"))
      (node (ref "U9") (pin "6") (pinfunction "GND_6") (pintype "power_in"))
      (node (ref "U9") (pin "64") (pinfunction "GND_64") (pintype "power_in"))
      (node (ref "U9") (pin "GND") (pinfunction "GND_GND") (pintype "power_in"))
      (node (ref "X1") (pin "2") (pinfunction "GND_2") (pintype "bidirectional"))
      (node (ref "X1") (pin "4") (pinfunction "GND_4") (pintype "bidirectional"))
    )
    (net (code "15") (name "LEDG1") (class "Default")
      (node (ref "R2") (pin "1") (pinfunction "1_1") (pintype "passive"))
      (node (ref "U9") (pin "27") (pinfunction "PB06_27") (pintype "bidirectional"))
    )
    (net (code "16") (name "LEDG2") (class "Default")
      (node (ref "R4") (pin "1") (pinfunction "1_1") (pintype "passive"))
      (node (ref "U9") (pin "19") (pinfunction "PB04_19") (pintype "bidirectional"))
    )
    (net (code "17") (name "LEDR1") (class "Default")
      (node (ref "R3") (pin "1") (pinfunction "1_1") (pintype "passive"))
      (node (ref "U9") (pin "28") (pinfunction "PB07_28") (pintype "bidirectional"))
    )
    (net (code "18") (name "LEDR2") (class "Default")
      (node (ref "R5") (pin "1") (pinfunction "1_1") (pintype "passive"))
      (node (ref "U9") (pin "20") (pinfunction "PB05_20") (pintype "bidirectional"))
    )
    (net (code "19") (name "MOD_IN") (class "Default")
      (node (ref "J3") (pin "10") (pinfunction "MOD_IN_10") (pintype "bidirectional"))
      (node (ref "U9") (pin "51") (pinfunction "PA20_51") (pintype "bidirectional"))
    )
    (net (code "20") (name "MOD_OUT") (class "Default")
      (node (ref "J3") (pin "8") (pinfunction "MOD_OUT_8") (pintype "bidirectional"))
      (node (ref "U9") (pin "50") (pinfunction "PA19_50") (pintype "bidirectional"))
    )
    (net (code "21") (name "Net-(C30-Pad1)") (class "Default")
      (node (ref "C30") (pin "1") (pinfunction "1_1") (pintype "bidirectional"))
      (node (ref "R6") (pin "1") (pinfunction "1_1") (pintype "passive"))
    )
    (net (code "22") (name "Net-(C30-Pad2)") (class "Default")
      (node (ref "C30") (pin "2") (pinfunction "2_2") (pintype "bidirectional"))
      (node (ref "C7") (pin "1") (pinfunction "1_1") (pintype "bidirectional"))
      (node (ref "R13") (pin "2") (pinfunction "2_2") (pintype "passive"))
    )
    (net (code "23") (name "Net-(C31-Pad1)") (class "Default")
      (node (ref "C31") (pin "1") (pinfunction "1_1") (pintype "bidirectional"))
      (node (ref "R7") (pin "1") (pinfunction "1_1") (pintype "passive"))
    )
    (net (code "24") (name "Net-(C31-Pad2)") (class "Default")
      (node (ref "C31") (pin "2") (pinfunction "2_2") (pintype "bidirectional"))
      (node (ref "C8") (pin "1") (pinfunction "1_1") (pintype "bidirectional"))
      (node (ref "R14") (pin "2") (pinfunction "2_2") (pintype "passive"))
    )
    (net (code "25") (name "Net-(FB1-P$1)") (class "Default")
      (node (ref "C21") (pin "1") (pinfunction "1_1") (pintype "bidirectional"))
      (node (ref "FB1") (pin "1") (pinfunction "P$1_1") (pintype "bidirectional"))
      (node (ref "U9") (pin "24") (pinfunction "ADVREFP_24") (pintype "bidirectional"))
      (node (ref "U9") (pin "25") (pinfunction "VDDANA_25") (pintype "power_in"))
    )
    (net (code "26") (name "Net-(J1-L)") (class "Default")
      (node (ref "J1") (pin "4") (pinfunction "L_4") (pintype "bidirectional"))
      (node (ref "R11") (pin "1") (pinfunction "1_1") (pintype "passive"))
    )
    (net (code "27") (name "Net-(J1-R)") (class "Default")
      (node (ref "J1") (pin "1") (pinfunction "R_1") (pintype "bidirectional"))
      (node (ref "R12") (pin "1") (pinfunction "1_1") (pintype "passive"))
    )
    (net (code "28") (name "Net-(J2-DBG_GPIO1)") (class "Default")
      (node (ref "J2") (pin "16") (pinfunction "DBG_GPIO1_16") (pintype "bidirectional"))
      (node (ref "U9") (pin "57") (pinfunction "PB14_57") (pintype "bidirectional"))
    )
    (net (code "29") (name "Net-(J2-DBG_GPIO2)") (class "Default")
      (node (ref "J2") (pin "19") (pinfunction "DBG_GPIO2_19") (pintype "bidirectional"))
      (node (ref "U9") (pin "58") (pinfunction "PB15_58") (pintype "bidirectional"))
    )
    (net (code "30") (name "Net-(L1-1)") (class "Default")
      (node (ref "L1") (pin "P$1") (pinfunction "1_P$1") (pintype "bidirectional"))
      (node (ref "U10") (pin "1") (pinfunction "SW_1") (pintype "bidirectional"))
      (node (ref "U10") (pin "2") (pinfunction "SW_2") (pintype "bidirectional"))
      (node (ref "U10") (pin "3") (pinfunction "SW_3") (pintype "bidirectional"))
    )
    (net (code "31") (name "Net-(L2-1)") (class "Default")
      (node (ref "L2") (pin "P$1") (pinfunction "1_P$1") (pintype "bidirectional"))
      (node (ref "U9") (pin "7") (pinfunction "VDDOUT_7") (pintype "power_in"))
    )
    (net (code "32") (name "Net-(L2-2)") (class "Default")
      (node (ref "C20") (pin "1") (pinfunction "1_1") (pintype "bidirectional"))
      (node (ref "C32") (pin "1") (pinfunction "1_1") (pintype "bidirectional"))
      (node (ref "L2") (pin "P$2") (pinfunction "2_P$2") (pintype "bidirectional"))
      (node (ref "U9") (pin "5") (pinfunction "VDDCORE_5") (pintype "power_in"))
    )
    (net (code "33") (name "Net-(LED1-CATHODE)") (class "Default")
      (node (ref "LED1") (pin "C") (pinfunction "CATHODE_C") (pintype "bidirectional"))
      (node (ref "R2") (pin "2") (pinfunction "2_2") (pintype "passive"))
    )
    (net (code "34") (name "Net-(LED2-CATHODE)") (class "Default")
      (node (ref "LED2") (pin "C") (pinfunction "CATHODE_C") (pintype "bidirectional"))
      (node (ref "R3") (pin "2") (pinfunction "2_2") (pintype "passive"))
    )
    (net (code "35") (name "Net-(LED3-CATHODE)") (class "Default")
      (node (ref "LED3") (pin "C") (pinfunction "CATHODE_C") (pintype "bidirectional"))
      (node (ref "R4") (pin "2") (pinfunction "2_2") (pintype "passive"))
    )
    (net (code "36") (name "Net-(LED4-CATHODE)") (class "Default")
      (node (ref "LED4") (pin "C") (pinfunction "CATHODE_C") (pintype "bidirectional"))
      (node (ref "R5") (pin "2") (pinfunction "2_2") (pintype "passive"))
    )
    (net (code "37") (name "Net-(P1-CW)") (class "Default")
      (node (ref "C5") (pin "2") (pinfunction "2_2") (pintype "bidirectional"))
      (node (ref "P1") (pin "2") (pinfunction "CW_2") (pintype "bidirectional"))
      (node (ref "R25") (pin "1") (pinfunction "1_1") (pintype "passive"))
      (node (ref "R6") (pin "2") (pinfunction "2_2") (pintype "passive"))
      (node (ref "U5") (pin "4") (pinfunction "-IN_4") (pintype "input"))
    )
    (net (code "38") (name "Net-(P1-W)") (class "Default")
      (node (ref "C10") (pin "2") (pinfunction "2_2") (pintype "bidirectional"))
      (node (ref "C5") (pin "1") (pinfunction "1_1") (pintype "bidirectional"))
      (node (ref "P1") (pin "3") (pinfunction "W_3") (pintype "bidirectional"))
      (node (ref "R25") (pin "2") (pinfunction "2_2") (pintype "passive"))
      (node (ref "R8") (pin "1") (pinfunction "1_1") (pintype "passive"))
      (node (ref "TP9") (pin "TESTPOINT") (pinfunction "TESTPOINT_TESTPOINT") (pintype "bidirectional"))
      (node (ref "U5") (pin "1") (pinfunction "OUT_1") (pintype "output"))
    )
    (net (code "39") (name "Net-(P2-CW)") (class "Default")
      (node (ref "C6") (pin "2") (pinfunction "2_2") (pintype "bidirectional"))
      (node (ref "P2") (pin "2") (pinfunction "CW_2") (pintype "bidirectional"))
      (node (ref "R28") (pin "1") (pinfunction "1_1") (pintype "passive"))
      (node (ref "R7") (pin "2") (pinfunction "2_2") (pintype "passive"))
      (node (ref "U6") (pin "4") (pinfunction "-IN_4") (pintype "input"))
    )
    (net (code "40") (name "Net-(P2-W)") (class "Default")
      (node (ref "C6") (pin "1") (pinfunction "1_1") (pintype "bidirectional"))
      (node (ref "C9") (pin "2") (pinfunction "2_2") (pintype "bidirectional"))
      (node (ref "P2") (pin "3") (pinfunction "W_3") (pintype "bidirectional"))
      (node (ref "R28") (pin "2") (pinfunction "2_2") (pintype "passive"))
      (node (ref "R9") (pin "1") (pinfunction "1_1") (pintype "passive"))
      (node (ref "TP10") (pin "TESTPOINT") (pinfunction "TESTPOINT_TESTPOINT") (pintype "bidirectional"))
      (node (ref "U6") (pin "1") (pinfunction "OUT_1") (pintype "output"))
    )
    (net (code "41") (name "Net-(R11-Pad2)") (class "Default")
      (node (ref "R11") (pin "2") (pinfunction "2_2") (pintype "passive"))
      (node (ref "R12") (pin "2") (pinfunction "2_2") (pintype "passive"))
      (node (ref "R14") (pin "1") (pinfunction "1_1") (pintype "passive"))
    )
    (net (code "42") (name "Net-(U2-OUT)") (class "Default")
      (node (ref "R13") (pin "1") (pinfunction "1_1") (pintype "passive"))
      (node (ref "U2") (pin "1") (pinfunction "OUT_1") (pintype "bidirectional"))
    )
    (net (code "43") (name "Net-(U3-CLK)") (class "Default")
      (node (ref "C3") (pin "1") (pinfunction "1_1") (pintype "bidirectional"))
      (node (ref "R32") (pin "2") (pinfunction "2_2") (pintype "passive"))
      (node (ref "U3") (pin "8") (pinfunction "CLK_8") (pintype "bidirectional"))
    )
    (net (code "44") (name "Net-(U3-GND)") (class "Default")
      (node (ref "C15") (pin "1") (pinfunction "1_1") (pintype "bidirectional"))
      (node (ref "U3") (pin "6") (pinfunction "GND_6") (pintype "bidirectional"))
    )
    (net (code "45") (name "Net-(U3-IN)") (class "Default")
      (node (ref "C9") (pin "1") (pinfunction "1_1") (pintype "bidirectional"))
      (node (ref "U3") (pin "5") (pinfunction "IN_5") (pintype "bidirectional"))
    )
    (net (code "46") (name "Net-(U4-CLK)") (class "Default")
      (node (ref "C4") (pin "1") (pinfunction "1_1") (pintype "bidirectional"))
      (node (ref "R33") (pin "2") (pinfunction "2_2") (pintype "passive"))
      (node (ref "U4") (pin "8") (pinfunction "CLK_8") (pintype "bidirectional"))
    )
    (net (code "47") (name "Net-(U4-GND)") (class "Default")
      (node (ref "C17") (pin "1") (pinfunction "1_1") (pintype "bidirectional"))
      (node (ref "U4") (pin "6") (pinfunction "GND_6") (pintype "bidirectional"))
    )
    (net (code "48") (name "Net-(U4-IN)") (class "Default")
      (node (ref "C10") (pin "1") (pinfunction "1_1") (pintype "bidirectional"))
      (node (ref "U4") (pin "5") (pinfunction "IN_5") (pintype "bidirectional"))
    )
    (net (code "49") (name "Net-(U5-+IN)") (class "Default")
      (node (ref "C25") (pin "2") (pinfunction "2_2") (pintype "bidirectional"))
      (node (ref "R17") (pin "2") (pinfunction "2_2") (pintype "passive"))
      (node (ref "R18") (pin "1") (pinfunction "1_1") (pintype "passive"))
      (node (ref "U5") (pin "3") (pinfunction "+IN_3") (pintype "input"))
    )
    (net (code "50") (name "Net-(U6-+IN)") (class "Default")
      (node (ref "C26") (pin "2") (pinfunction "2_2") (pintype "bidirectional"))
      (node (ref "R19") (pin "2") (pinfunction "2_2") (pintype "passive"))
      (node (ref "R20") (pin "1") (pinfunction "1_1") (pintype "passive"))
      (node (ref "U6") (pin "3") (pinfunction "+IN_3") (pintype "input"))
    )
    (net (code "51") (name "Net-(U7-+IN)") (class "Default")
      (node (ref "C28") (pin "2") (pinfunction "2_2") (pintype "bidirectional"))
      (node (ref "R21") (pin "1") (pinfunction "1_1") (pintype "passive"))
      (node (ref "R22") (pin "2") (pinfunction "2_2") (pintype "passive"))
      (node (ref "U7") (pin "3") (pinfunction "+IN_3") (pintype "input"))
    )
    (net (code "52") (name "Net-(U7--IN)") (class "Default")
      (node (ref "C12") (pin "2") (pinfunction "2_2") (pintype "bidirectional"))
      (node (ref "R15") (pin "1") (pinfunction "1_1") (pintype "passive"))
      (node (ref "R8") (pin "2") (pinfunction "2_2") (pintype "passive"))
      (node (ref "U7") (pin "4") (pinfunction "-IN_4") (pintype "input"))
    )
    (net (code "53") (name "Net-(U8-+IN)") (class "Default")
      (node (ref "C29") (pin "2") (pinfunction "2_2") (pintype "bidirectional"))
      (node (ref "R23") (pin "2") (pinfunction "2_2") (pintype "passive"))
      (node (ref "R24") (pin "1") (pinfunction "1_1") (pintype "passive"))
      (node (ref "U8") (pin "3") (pinfunction "+IN_3") (pintype "input"))
    )
    (net (code "54") (name "Net-(U8--IN)") (class "Default")
      (node (ref "C13") (pin "2") (pinfunction "2_2") (pintype "bidirectional"))
      (node (ref "R16") (pin "1") (pinfunction "1_1") (pintype "passive"))
      (node (ref "R9") (pin "2") (pinfunction "2_2") (pintype "passive"))
      (node (ref "U8") (pin "4") (pinfunction "-IN_4") (pintype "input"))
    )
    (net (code "55") (name "Net-(U9-BIASH)") (class "Default")
      (node (ref "U9") (pin "36") (pinfunction "BIASH_36") (pintype "bidirectional"))
      (node (ref "U9") (pin "37") (pinfunction "BIASL_37") (pintype "bidirectional"))
    )
    (net (code "56") (name "Net-(U9-CAPH)") (class "Default")
      (node (ref "U9") (pin "33") (pinfunction "CAPH_33") (pintype "bidirectional"))
      (node (ref "U9") (pin "34") (pinfunction "CAPL_34") (pintype "bidirectional"))
    )
    (net (code "57") (name "Net-(U9-PA02)") (class "Default")
      (node (ref "R1") (pin "2") (pinfunction "2_2") (pintype "passive"))
      (node (ref "R10") (pin "1") (pinfunction "1_1") (pintype "passive"))
      (node (ref "U9") (pin "3") (pinfunction "PA02_3") (pintype "bidirectional"))
    )
    (net (code "58") (name "Net-(U9-PB01)") (class "Default")
      (node (ref "TP8") (pin "TESTPOINT") (pinfunction "TESTPOINT_TESTPOINT") (pintype "bidirectional"))
      (node (ref "U9") (pin "12") (pinfunction "PB01_12") (pintype "bidirectional"))
    )
    (net (code "59") (name "Net-(U10-FB)") (class "Default")
      (node (ref "R34") (pin "2") (pinfunction "2_2") (pintype "passive"))
      (node (ref "R35") (pin "1") (pinfunction "1_1") (pintype "passive"))
      (node (ref "U10") (pin "5") (pinfunction "FB_5") (pintype "bidirectional"))
    )
    (net (code "60") (name "Net-(U10-PG)") (class "Default")
      (node (ref "R29") (pin "1") (pinfunction "1_1") (pintype "passive"))
      (node (ref "U10") (pin "4") (pinfunction "PG_4") (pintype "bidirectional"))
    )
    (net (code "61") (name "Net-(U10-SS{slash}TR)") (class "Default")
      (node (ref "C14") (pin "2") (pinfunction "2_2") (pintype "bidirectional"))
      (node (ref "U10") (pin "9") (pinfunction "SS/TR_9") (pintype "bidirectional"))
    )
    (net (code "62") (name "PPS") (class "Default")
      (node (ref "J3") (pin "7") (pinfunction "PPS_7") (pintype "bidirectional"))
      (node (ref "U9") (pin "49") (pinfunction "PA18_49") (pintype "bidirectional"))
    )
    (net (code "63") (name "SCL") (class "Default")
      (node (ref "J3") (pin "5") (pinfunction "SCL_5") (pintype "bidirectional"))
      (node (ref "U9") (pin "60") (pinfunction "PA24_60") (pintype "bidirectional"))
    )
    (net (code "64") (name "SDA") (class "Default")
      (node (ref "J3") (pin "6") (pinfunction "SDA_6") (pintype "bidirectional"))
      (node (ref "U9") (pin "59") (pinfunction "PA23_59") (pintype "bidirectional"))
    )
    (net (code "65") (name "SPEC2_GATED") (class "Default")
      (node (ref "C16") (pin "1") (pinfunction "1_1") (pintype "bidirectional"))
      (node (ref "Q1") (pin "3") (pinfunction "D_3") (pintype "passive"))
      (node (ref "R19") (pin "1") (pinfunction "1_1") (pintype "passive"))
      (node (ref "R23") (pin "1") (pinfunction "1_1") (pintype "passive"))
      (node (ref "R32") (pin "1") (pinfunction "1_1") (pintype "passive"))
      (node (ref "U3") (pin "1") (pinfunction "VDD_1") (pintype "bidirectional"))
      (node (ref "U6") (pin "5") (pinfunction "V+_5") (pintype "power_in"))
      (node (ref "U8") (pin "5") (pinfunction "V+_5") (pintype "power_in"))
    )
    (net (code "66") (name "SPEC2_OUT") (class "Default")
      (node (ref "TP2") (pin "TESTPOINT") (pinfunction "TESTPOINT_TESTPOINT") (pintype "bidirectional"))
      (node (ref "U3") (pin "3") (pinfunction "OUT_3") (pintype "bidirectional"))
      (node (ref "U9") (pin "16") (pinfunction "PA05_16") (pintype "bidirectional"))
    )
    (net (code "67") (name "SPEC2_POWER") (class "Default")
      (node (ref "Q1") (pin "1") (pinfunction "G_1") (pintype "passive"))
      (node (ref "R30") (pin "1") (pinfunction "1_1") (pintype "passive"))
      (node (ref "TP4") (pin "TESTPOINT") (pinfunction "TESTPOINT_TESTPOINT") (pintype "bidirectional"))
      (node (ref "U9") (pin "26") (pinfunction "PA08_26") (pintype "bidirectional"))
    )
    (net (code "68") (name "SPEC2_RESET") (class "Default")
      (node (ref "TP3") (pin "TESTPOINT") (pinfunction "TESTPOINT_TESTPOINT") (pintype "bidirectional"))
      (node (ref "U3") (pin "7") (pinfunction "RESET_7") (pintype "bidirectional"))
      (node (ref "U9") (pin "22") (pinfunction "PA07_22") (pintype "bidirectional"))
    )
    (net (code "69") (name "SPEC2_STROBE") (class "Default")
      (node (ref "TP5") (pin "TESTPOINT") (pinfunction "TESTPOINT_TESTPOINT") (pintype "bidirectional"))
      (node (ref "U3") (pin "4") (pinfunction "STROBE_4") (pintype "bidirectional"))
      (node (ref "U9") (pin "21") (pinfunction "PA06_21") (pintype "bidirectional"))
    )
    (net (code "70") (name "SPEC_GATED") (class "Default")
      (node (ref "C11") (pin "2") (pinfunction "2_2") (pintype "bidirectional"))
      (node (ref "C18") (pin "1") (pinfunction "1_1") (pintype "bidirectional"))
      (node (ref "C27") (pin "2") (pinfunction "2_2") (pintype "bidirectional"))
      (node (ref "Q2") (pin "3") (pinfunction "D_3") (pintype "passive"))
      (node (ref "R17") (pin "1") (pinfunction "1_1") (pintype "passive"))
      (node (ref "R22") (pin "1") (pinfunction "1_1") (pintype "passive"))
      (node (ref "R33") (pin "1") (pinfunction "1_1") (pintype "passive"))
      (node (ref "U2") (pin "2") (pinfunction "VDD_2") (pintype "bidirectional"))
      (node (ref "U4") (pin "1") (pinfunction "VDD_1") (pintype "bidirectional"))
      (node (ref "U5") (pin "5") (pinfunction "V+_5") (pintype "power_in"))
      (node (ref "U7") (pin "5") (pinfunction "V+_5") (pintype "power_in"))
    )
    (net (code "71") (name "SPEC_OUT") (class "Default")
      (node (ref "TP1") (pin "TESTPOINT") (pinfunction "TESTPOINT_TESTPOINT") (pintype "bidirectional"))
      (node (ref "U4") (pin "3") (pinfunction "OUT_3") (pintype "bidirectional"))
      (node (ref "U9") (pin "15") (pinfunction "PA04_15") (pintype "bidirectional"))
    )
    (net (code "72") (name "SPEC_POWER") (class "Default")
      (node (ref "Q2") (pin "1") (pinfunction "G_1") (pintype "passive"))
      (node (ref "R31") (pin "1") (pinfunction "1_1") (pintype "passive"))
    )
    (net (code "73") (name "SPEC_RESET") (class "Default")
      (node (ref "TP7") (pin "TESTPOINT") (pinfunction "TESTPOINT_TESTPOINT") (pintype "bidirectional"))
      (node (ref "U4") (pin "7") (pinfunction "RESET_7") (pintype "bidirectional"))
      (node (ref "U9") (pin "11") (pinfunction "PB00_11") (pintype "bidirectional"))
    )
    (net (code "74") (name "SPEC_STROBE") (class "Default")
      (node (ref "TP6") (pin "TESTPOINT") (pinfunction "TESTPOINT_TESTPOINT") (pintype "bidirectional"))
      (node (ref "U4") (pin "4") (pinfunction "STROBE_4") (pintype "bidirectional"))
      (node (ref "U9") (pin "30") (pinfunction "PA10_30") (pintype "bidirectional"))
    )
    (net (code "75") (name "USB+") (class "Default")
      (node (ref "J3") (pin "11") (pinfunction "USB_D+_11") (pintype "bidirectional"))
      (node (ref "U9") (pin "63") (pinfunction "PA26_63") (pintype "bidirectional"))
    )
    (net (code "76") (name "USB-") (class "Default")
      (node (ref "J3") (pin "12") (pinfunction "USB_D-_12") (pintype "bidirectional"))
      (node (ref "U9") (pin "62") (pinfunction "PA25_62") (pintype "bidirectional"))
    )
    (net (code "77") (name "unconnected-(J1-LDET-Pad3)") (class "Default")
      (node (ref "J1") (pin "3") (pinfunction "LDET_3") (pintype "bidirectional"))
    )
    (net (code "78") (name "unconnected-(J1-RDET-Pad2)") (class "Default")
      (node (ref "J1") (pin "2") (pinfunction "RDET_2") (pintype "bidirectional"))
    )
    (net (code "79") (name "unconnected-(J3-USB_VBUS-Pad13)") (class "Default")
      (node (ref "J3") (pin "13") (pinfunction "USB_VBUS_13") (pintype "bidirectional"))
    )
    (net (code "80") (name "unconnected-(J4-SWO-Pad6)") (class "Default")
      (node (ref "J4") (pin "6") (pinfunction "SWO_6") (pintype "bidirectional"))
    )
    (net (code "81") (name "unconnected-(P1-CCW-Pad1)") (class "Default")
      (node (ref "P1") (pin "1") (pinfunction "CCW_1") (pintype "bidirectional"))
    )
    (net (code "82") (name "unconnected-(P2-CCW-Pad1)") (class "Default")
      (node (ref "P2") (pin "1") (pinfunction "CCW_1") (pintype "bidirectional"))
    )
    (net (code "83") (name "unconnected-(U9-PA09-Pad29)") (class "Default")
      (node (ref "U9") (pin "29") (pinfunction "PA09_29") (pintype "bidirectional"))
    )
    (net (code "84") (name "unconnected-(U9-PA13-Pad40)") (class "Default")
      (node (ref "U9") (pin "40") (pinfunction "PA13_40") (pintype "bidirectional"))
    )
    (net (code "85") (name "unconnected-(U9-PA14-Pad41)") (class "Default")
      (node (ref "U9") (pin "41") (pinfunction "PA14_41") (pintype "bidirectional"))
    )
    (net (code "86") (name "unconnected-(U9-PA16-Pad43)") (class "Default")
      (node (ref "U9") (pin "43") (pinfunction "PA16_43") (pintype "bidirectional"))
    )
    (net (code "87") (name "unconnected-(U9-PA17-Pad44)") (class "Default")
      (node (ref "U9") (pin "44") (pinfunction "PA17_44") (pintype "bidirectional"))
    )
    (net (code "88") (name "unconnected-(U9-PA21-Pad55)") (class "Default")
      (node (ref "U9") (pin "55") (pinfunction "PA21_55") (pintype "bidirectional"))
    )
    (net (code "89") (name "unconnected-(U9-PA22-Pad56)") (class "Default")
      (node (ref "U9") (pin "56") (pinfunction "PA22_56") (pintype "bidirectional"))
    )
    (net (code "90") (name "unconnected-(U9-PB12-Pad53)") (class "Default")
      (node (ref "U9") (pin "53") (pinfunction "PB12_53") (pintype "bidirectional"))
    )
    (net (code "91") (name "unconnected-(U9-PB13-Pad54)") (class "Default")
      (node (ref "U9") (pin "54") (pinfunction "PB13_54") (pintype "bidirectional"))
    )
    (net (code "92") (name "unconnected-(U9-XIN32-Pad17)") (class "Default")
      (node (ref "U9") (pin "17") (pinfunction "XIN32_17") (pintype "bidirectional"))
    )
    (net (code "93") (name "unconnected-(U9-XOUT32-Pad18)") (class "Default")
      (node (ref "U9") (pin "18") (pinfunction "XOUT32_18") (pintype "bidirectional"))
    )
    (net (code "94") (name "~{AUDIO_RESET}") (class "Default")
      (node (ref "J2") (pin "20") (pinfunction "DBG_~{RESET}_20") (pintype "bidirectional"))
      (node (ref "J4") (pin "3") (pinfunction "~{RESET}_3") (pintype "bidirectional"))
      (node (ref "S1") (pin "2") (pinfunction "P$2_2") (pintype "passive"))
      (node (ref "U9") (pin "4") (pinfunction "~{RESET}_4") (pintype "bidirectional"))
    )
    (net (code "95") (name "~{FLASH_CS}") (class "Default")
      (node (ref "!CS") (pin "TESTPOINT") (pinfunction "TESTPOINT_TESTPOINT") (pintype "bidirectional"))
      (node (ref "U1") (pin "P4") (pinfunction "~{CS}_P4") (pintype "bidirectional"))
      (node (ref "U9") (pin "42") (pinfunction "PA15_42") (pintype "bidirectional"))
    )
    (net (code "96") (name "~{FLASH_RESET}") (class "Default")
      (node (ref "U1") (pin "P3") (pinfunction "~{RESET}_P3") (pintype "bidirectional"))
      (node (ref "U9") (pin "48") (pinfunction "PB11_48") (pintype "bidirectional"))
    )
  )
)
